# sheet_6.net
KiCad netlist of a schematic drawn in Altium Designer
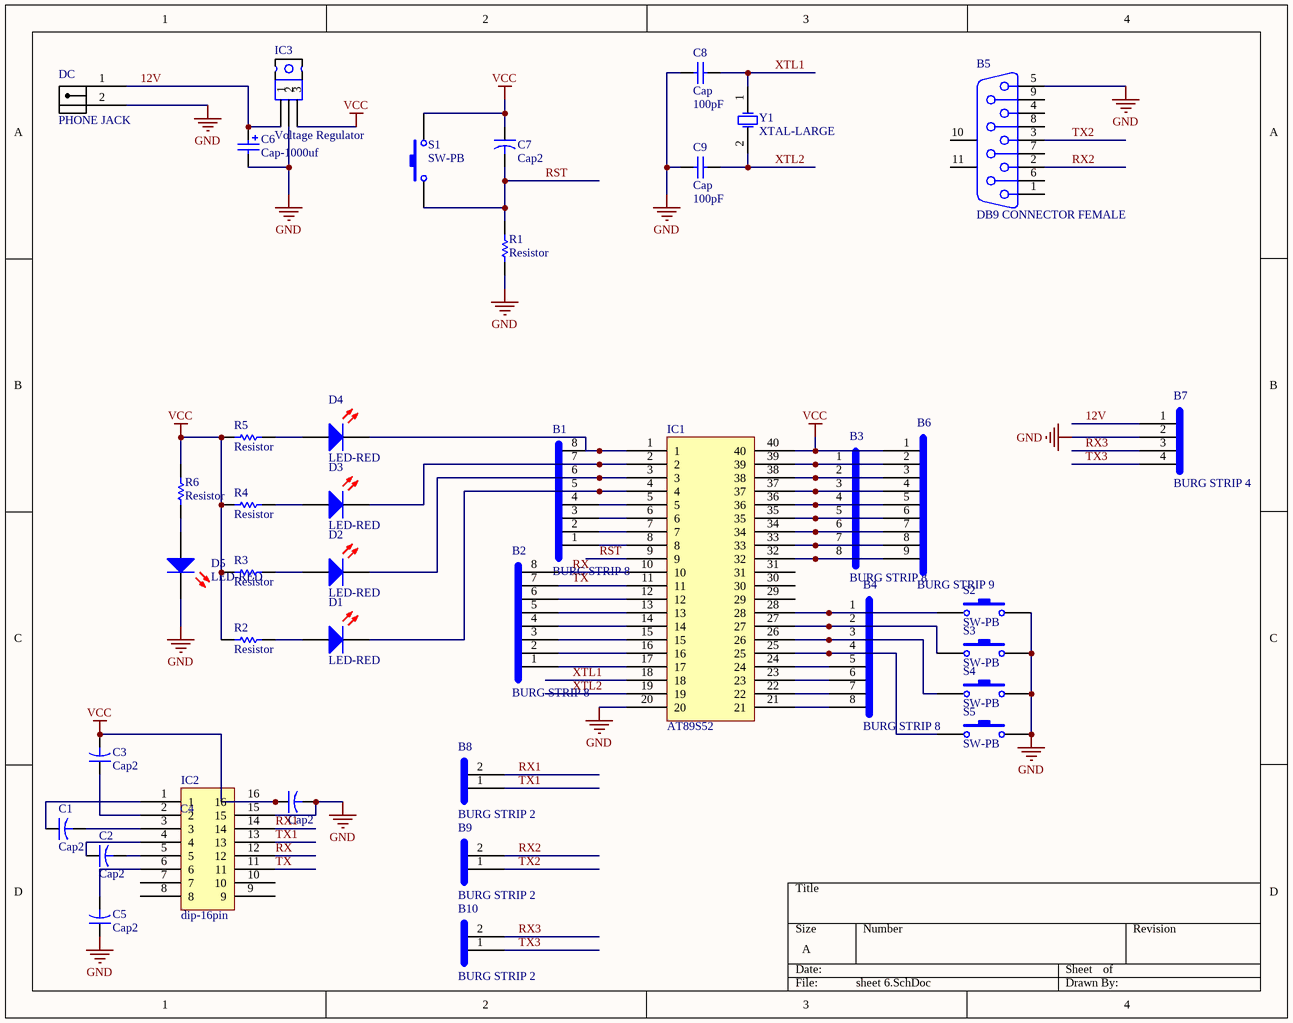
[diagram p0: sheet 6.SchDoc]

(export (version "E")
  (design (tool "Eeschema 10.0.6"))
  (components
    (comp (ref "B1")
      (value "BURG STRIP 8")
      (footprint "bergstrip-8pin")
      (libsource (lib "Devindia_v4.0") (part "BURG STRIP 8"))
    )
    (comp (ref "B2")
      (value "BURG STRIP 8")
      (footprint "bergstrip-8pin")
      (libsource (lib "Devindia_v4.0") (part "BURG STRIP 8"))
    )
    (comp (ref "B3")
      (value "BURG STRIP 8")
      (footprint "bergstrip-8pin")
      (libsource (lib "Devindia_v4.0") (part "BURG STRIP 8"))
    )
    (comp (ref "B4")
      (value "BURG STRIP 8")
      (footprint "bergstrip-8pin")
      (libsource (lib "Devindia_v4.0") (part "BURG STRIP 8"))
    )
    (comp (ref "B5")
      (value "DB9 CONNECTOR FEMALE")
      (footprint "DB9 CONNECTOR FEMALE")
      (libsource (lib "Devindia_v4.0") (part "DB9 CONNECTOR FEMALE"))
    )
    (comp (ref "B6")
      (value "BURG STRIP 9")
      (footprint "bergstrip-9pin")
      (libsource (lib "Devindia_v4.0") (part "BURG STRIP 9"))
    )
    (comp (ref "B7")
      (value "BURG STRIP 4")
      (footprint "bergstrip-4pin")
      (libsource (lib "Devindia_v4.0") (part "BURG STRIP 4"))
    )
    (comp (ref "B8")
      (value "BURG STRIP 2")
      (footprint "bergstrip-2pin")
      (libsource (lib "Devindia_v4.0") (part "BURG STRIP 2"))
    )
    (comp (ref "B9")
      (value "BURG STRIP 2")
      (footprint "bergstrip-2pin")
      (libsource (lib "Devindia_v4.0") (part "BURG STRIP 2"))
    )
    (comp (ref "B10")
      (value "BURG STRIP 2")
      (footprint "bergstrip-2pin")
      (libsource (lib "Devindia_v4.0") (part "BURG STRIP 2"))
    )
    (comp (ref "C1") (value "Cap2") (footprint "CAP-100uf") (libsource (lib "Devindia_v4.0") (part "Cap2")))
    (comp (ref "C2") (value "Cap2") (footprint "CAP-100uf") (libsource (lib "Devindia_v4.0") (part "Cap2")))
    (comp (ref "C3") (value "Cap2") (footprint "CAP-100uf") (libsource (lib "Devindia_v4.0") (part "Cap2")))
    (comp (ref "C4") (value "Cap2") (footprint "CAP-100uf") (libsource (lib "Devindia_v4.0") (part "Cap2")))
    (comp (ref "C5") (value "Cap2") (footprint "CAP-100uf") (libsource (lib "Devindia_v4.0") (part "Cap2")))
    (comp (ref "C6")
      (value "Cap-1000uf")
      (footprint "CAP-1000uf")
      (libsource (lib "Devindia_v4.0") (part "Cap-1000uf"))
    )
    (comp (ref "C7") (value "Cap2") (footprint "CAP-100uf") (libsource (lib "Devindia_v4.0") (part "Cap2")))
    (comp (ref "C8")
      (value "Cap")
      (footprint "CAP")
      (description "Capacitor")
      (fields (field (name "ALTIUM_VALUE") "100pF") (field (name "PUBLISHER") "Altium Limited"))
      (libsource (lib "Devindia_v4.0") (part "Cap"))
    )
    (comp (ref "C9")
      (value "Cap")
      (footprint "CAP")
      (description "Capacitor")
      (fields (field (name "ALTIUM_VALUE") "100pF") (field (name "PUBLISHER") "Altium Limited"))
      (libsource (lib "Devindia_v4.0") (part "Cap"))
    )
    (comp (ref "D1")
      (value "LED-RED")
      (footprint "LED-RED")
      (description "Typical BLUE SiC LED")
      (fields (field (name "PUBLISHER") "Altium Limited"))
      (libsource (lib "Devindia_v4.0") (part "LED-RED"))
    )
    (comp (ref "D2")
      (value "LED-RED")
      (footprint "LED-RED")
      (description "Typical BLUE SiC LED")
      (fields (field (name "PUBLISHER") "Altium Limited"))
      (libsource (lib "Devindia_v4.0") (part "LED-RED"))
    )
    (comp (ref "D3")
      (value "LED-RED")
      (footprint "LED-RED")
      (description "Typical BLUE SiC LED")
      (fields (field (name "PUBLISHER") "Altium Limited"))
      (libsource (lib "Devindia_v4.0") (part "LED-RED"))
    )
    (comp (ref "D4")
      (value "LED-RED")
      (footprint "LED-RED")
      (description "Typical BLUE SiC LED")
      (fields (field (name "PUBLISHER") "Altium Limited"))
      (libsource (lib "Devindia_v4.0") (part "LED-RED"))
    )
    (comp (ref "D5")
      (value "LED-RED")
      (footprint "LED-RED")
      (description "Typical BLUE SiC LED")
      (fields (field (name "PUBLISHER") "Altium Limited"))
      (libsource (lib "Devindia_v4.0") (part "LED-RED"))
    )
    (comp (ref "DC")
      (value "PHONE JACK")
      (footprint "PHONE JACK")
      (libsource (lib "Devindia_v4.0") (part "PHONE JACK"))
    )
    (comp (ref "IC1")
      (value "AT89S52")
      (footprint "AT89S52")
      (libsource (lib "Devindia_v4.0") (part "AT89S52"))
    )
    (comp (ref "IC2")
      (value "dip-16pin")
      (footprint "dip-16pin")
      (libsource (lib "Devindia_v4.0") (part "dip-16pin"))
    )
    (comp (ref "IC3")
      (value "Voltage Regulator")
      (footprint "7805 WITH HEAT-SINK")
      (libsource (lib "Devindia_v4.0") (part "7805 HEATSINK"))
    )
    (comp (ref "R1")
      (value "Resistor")
      (footprint "res-2.54x4")
      (libsource (lib "Devindia_v4.0") (part "Resistor 2.54x4"))
    )
    (comp (ref "R2")
      (value "Resistor")
      (footprint "res-2.54x4")
      (libsource (lib "Devindia_v4.0") (part "Resistor 2.54x4"))
    )
    (comp (ref "R3")
      (value "Resistor")
      (footprint "res-2.54x4")
      (libsource (lib "Devindia_v4.0") (part "Resistor 2.54x4"))
    )
    (comp (ref "R4")
      (value "Resistor")
      (footprint "res-2.54x4")
      (libsource (lib "Devindia_v4.0") (part "Resistor 2.54x4"))
    )
    (comp (ref "R5")
      (value "Resistor")
      (footprint "res-2.54x4")
      (libsource (lib "Devindia_v4.0") (part "Resistor 2.54x4"))
    )
    (comp (ref "R6")
      (value "Resistor")
      (footprint "res-2.54x4")
      (libsource (lib "Devindia_v4.0") (part "Resistor 2.54x4"))
    )
    (comp (ref "S1")
      (value "SW-PB")
      (footprint "sw-pb")
      (description "Switch")
      (fields (field (name "PUBLISHER") "Altium Limited"))
      (libsource (lib "Devindia_v4.0") (part "SW-PB"))
    )
    (comp (ref "S2")
      (value "SW-PB")
      (footprint "sw-pb")
      (description "Switch")
      (fields (field (name "PUBLISHER") "Altium Limited"))
      (libsource (lib "Devindia_v4.0") (part "SW-PB"))
    )
    (comp (ref "S3")
      (value "SW-PB")
      (footprint "sw-pb")
      (description "Switch")
      (fields (field (name "PUBLISHER") "Altium Limited"))
      (libsource (lib "Devindia_v4.0") (part "SW-PB"))
    )
    (comp (ref "S4")
      (value "SW-PB")
      (footprint "sw-pb")
      (description "Switch")
      (fields (field (name "PUBLISHER") "Altium Limited"))
      (libsource (lib "Devindia_v4.0") (part "SW-PB"))
    )
    (comp (ref "S5")
      (value "SW-PB")
      (footprint "sw-pb")
      (description "Switch")
      (fields (field (name "PUBLISHER") "Altium Limited"))
      (libsource (lib "Devindia_v4.0") (part "SW-PB"))
    )
    (comp (ref "Y1")
      (value "XTAL-LARGE")
      (footprint "XTAL-LARGE")
      (description "Crystal Oscillator")
      (fields (field (name "PUBLISHER") "Altium Limited"))
      (libsource (lib "Devindia_v4.0") (part "XTAL-LARGE"))
    )
  )
  (nets
    (net (code "1") (name "/12V") (class "Default")
      (node (ref "B7") (pin "1") (pinfunction "1_1") (pintype "passive"))
      (node (ref "C6") (pin "1") (pinfunction "1_1") (pintype "passive"))
      (node (ref "DC") (pin "1") (pinfunction "1_1") (pintype "passive"))
      (node (ref "IC3") (pin "1") (pinfunction "1_1") (pintype "passive"))
    )
    (net (code "2") (name "/RST") (class "Default")
      (node (ref "C7") (pin "2") (pinfunction "2_2") (pintype "passive"))
      (node (ref "IC1") (pin "9") (pinfunction "9_9") (pintype "passive"))
      (node (ref "R1") (pin "2") (pinfunction "2_2") (pintype "passive"))
      (node (ref "S1") (pin "1") (pinfunction "1_1") (pintype "passive"))
    )
    (net (code "3") (name "/RX") (class "Default")
      (node (ref "B2") (pin "8") (pinfunction "8_8") (pintype "passive"))
      (node (ref "IC1") (pin "10") (pinfunction "10_10") (pintype "passive"))
      (node (ref "IC2") (pin "12") (pinfunction "12_12") (pintype "passive"))
    )
    (net (code "4") (name "/RX1") (class "Default")
      (node (ref "B8") (pin "2") (pinfunction "2_2") (pintype "passive"))
      (node (ref "IC2") (pin "14") (pinfunction "14_14") (pintype "passive"))
    )
    (net (code "5") (name "/RX2") (class "Default")
      (node (ref "B5") (pin "2") (pinfunction "2_2") (pintype "passive"))
      (node (ref "B9") (pin "2") (pinfunction "2_2") (pintype "passive"))
    )
    (net (code "6") (name "/RX3") (class "Default")
      (node (ref "B10") (pin "2") (pinfunction "2_2") (pintype "passive"))
      (node (ref "B7") (pin "3") (pinfunction "3_3") (pintype "passive"))
    )
    (net (code "7") (name "/TX") (class "Default")
      (node (ref "B2") (pin "7") (pinfunction "7_7") (pintype "passive"))
      (node (ref "IC1") (pin "11") (pinfunction "11_11") (pintype "passive"))
      (node (ref "IC2") (pin "11") (pinfunction "11_11") (pintype "passive"))
    )
    (net (code "8") (name "/TX1") (class "Default")
      (node (ref "B8") (pin "1") (pinfunction "1_1") (pintype "passive"))
      (node (ref "IC2") (pin "13") (pinfunction "13_13") (pintype "passive"))
    )
    (net (code "9") (name "/TX2") (class "Default")
      (node (ref "B5") (pin "3") (pinfunction "3_3") (pintype "passive"))
      (node (ref "B9") (pin "1") (pinfunction "1_1") (pintype "passive"))
    )
    (net (code "10") (name "/TX3") (class "Default")
      (node (ref "B10") (pin "1") (pinfunction "1_1") (pintype "passive"))
      (node (ref "B7") (pin "4") (pinfunction "4_4") (pintype "passive"))
    )
    (net (code "11") (name "/XTL1") (class "Default")
      (node (ref "C8") (pin "2") (pinfunction "2_2") (pintype "passive"))
      (node (ref "IC1") (pin "18") (pinfunction "18_18") (pintype "passive"))
      (node (ref "Y1") (pin "1") (pinfunction "OSC1_1") (pintype "passive"))
    )
    (net (code "12") (name "/XTL2") (class "Default")
      (node (ref "C9") (pin "2") (pinfunction "2_2") (pintype "passive"))
      (node (ref "IC1") (pin "19") (pinfunction "19_19") (pintype "passive"))
      (node (ref "Y1") (pin "2") (pinfunction "OSC2_2") (pintype "passive"))
    )
    (net (code "13") (name "GND") (class "Default")
      (node (ref "B5") (pin "5") (pinfunction "5_5") (pintype "passive"))
      (node (ref "B7") (pin "2") (pinfunction "2_2") (pintype "passive"))
      (node (ref "C4") (pin "2") (pinfunction "2_2") (pintype "passive"))
      (node (ref "C5") (pin "1") (pinfunction "1_1") (pintype "passive"))
      (node (ref "C6") (pin "2") (pinfunction "2_2") (pintype "passive"))
      (node (ref "C8") (pin "1") (pinfunction "1_1") (pintype "passive"))
      (node (ref "C9") (pin "1") (pinfunction "1_1") (pintype "passive"))
      (node (ref "D5") (pin "2") (pinfunction "K_2") (pintype "passive"))
      (node (ref "DC") (pin "2") (pinfunction "2_2") (pintype "passive"))
      (node (ref "IC1") (pin "20") (pinfunction "20_20") (pintype "passive"))
      (node (ref "IC2") (pin "15") (pinfunction "15_15") (pintype "passive"))
      (node (ref "IC3") (pin "2") (pinfunction "2_2") (pintype "passive"))
      (node (ref "R1") (pin "1") (pinfunction "1_1") (pintype "passive"))
      (node (ref "S2") (pin "2") (pinfunction "2_2") (pintype "passive"))
      (node (ref "S3") (pin "2") (pinfunction "2_2") (pintype "passive"))
      (node (ref "S4") (pin "2") (pinfunction "2_2") (pintype "passive"))
      (node (ref "S5") (pin "2") (pinfunction "2_2") (pintype "passive"))
    )
    (net (code "14") (name "Net-(B1-Pad1)") (class "Default")
      (node (ref "B1") (pin "1") (pinfunction "1_1") (pintype "passive"))
      (node (ref "IC1") (pin "8") (pinfunction "8_8") (pintype "passive"))
    )
    (net (code "15") (name "Net-(B1-Pad2)") (class "Default")
      (node (ref "B1") (pin "2") (pinfunction "2_2") (pintype "passive"))
      (node (ref "IC1") (pin "7") (pinfunction "7_7") (pintype "passive"))
    )
    (net (code "16") (name "Net-(B1-Pad3)") (class "Default")
      (node (ref "B1") (pin "3") (pinfunction "3_3") (pintype "passive"))
      (node (ref "IC1") (pin "6") (pinfunction "6_6") (pintype "passive"))
    )
    (net (code "17") (name "Net-(B1-Pad4)") (class "Default")
      (node (ref "B1") (pin "4") (pinfunction "4_4") (pintype "passive"))
      (node (ref "IC1") (pin "5") (pinfunction "5_5") (pintype "passive"))
    )
    (net (code "18") (name "Net-(B2-Pad1)") (class "Default")
      (node (ref "B2") (pin "1") (pinfunction "1_1") (pintype "passive"))
      (node (ref "IC1") (pin "17") (pinfunction "17_17") (pintype "passive"))
    )
    (net (code "19") (name "Net-(B2-Pad2)") (class "Default")
      (node (ref "B2") (pin "2") (pinfunction "2_2") (pintype "passive"))
      (node (ref "IC1") (pin "16") (pinfunction "16_16") (pintype "passive"))
    )
    (net (code "20") (name "Net-(B2-Pad3)") (class "Default")
      (node (ref "B2") (pin "3") (pinfunction "3_3") (pintype "passive"))
      (node (ref "IC1") (pin "15") (pinfunction "15_15") (pintype "passive"))
    )
    (net (code "21") (name "Net-(B2-Pad4)") (class "Default")
      (node (ref "B2") (pin "4") (pinfunction "4_4") (pintype "passive"))
      (node (ref "IC1") (pin "14") (pinfunction "14_14") (pintype "passive"))
    )
    (net (code "22") (name "Net-(B2-Pad5)") (class "Default")
      (node (ref "B2") (pin "5") (pinfunction "5_5") (pintype "passive"))
      (node (ref "IC1") (pin "13") (pinfunction "13_13") (pintype "passive"))
    )
    (net (code "23") (name "Net-(B2-Pad6)") (class "Default")
      (node (ref "B2") (pin "6") (pinfunction "6_6") (pintype "passive"))
      (node (ref "IC1") (pin "12") (pinfunction "12_12") (pintype "passive"))
    )
    (net (code "24") (name "Net-(B3-Pad1)") (class "Default")
      (node (ref "B3") (pin "1") (pinfunction "1_1") (pintype "passive"))
      (node (ref "B6") (pin "2") (pinfunction "2_2") (pintype "passive"))
      (node (ref "IC1") (pin "39") (pinfunction "39_39") (pintype "passive"))
    )
    (net (code "25") (name "Net-(B3-Pad2)") (class "Default")
      (node (ref "B3") (pin "2") (pinfunction "2_2") (pintype "passive"))
      (node (ref "B6") (pin "3") (pinfunction "3_3") (pintype "passive"))
      (node (ref "IC1") (pin "38") (pinfunction "38_38") (pintype "passive"))
    )
    (net (code "26") (name "Net-(B3-Pad3)") (class "Default")
      (node (ref "B3") (pin "3") (pinfunction "3_3") (pintype "passive"))
      (node (ref "B6") (pin "4") (pinfunction "4_4") (pintype "passive"))
      (node (ref "IC1") (pin "37") (pinfunction "37_37") (pintype "passive"))
    )
    (net (code "27") (name "Net-(B3-Pad4)") (class "Default")
      (node (ref "B3") (pin "4") (pinfunction "4_4") (pintype "passive"))
      (node (ref "B6") (pin "5") (pinfunction "5_5") (pintype "passive"))
      (node (ref "IC1") (pin "36") (pinfunction "36_36") (pintype "passive"))
    )
    (net (code "28") (name "Net-(B3-Pad5)") (class "Default")
      (node (ref "B3") (pin "5") (pinfunction "5_5") (pintype "passive"))
      (node (ref "B6") (pin "6") (pinfunction "6_6") (pintype "passive"))
      (node (ref "IC1") (pin "35") (pinfunction "35_35") (pintype "passive"))
    )
    (net (code "29") (name "Net-(B3-Pad6)") (class "Default")
      (node (ref "B3") (pin "6") (pinfunction "6_6") (pintype "passive"))
      (node (ref "B6") (pin "7") (pinfunction "7_7") (pintype "passive"))
      (node (ref "IC1") (pin "34") (pinfunction "34_34") (pintype "passive"))
    )
    (net (code "30") (name "Net-(B3-Pad7)") (class "Default")
      (node (ref "B3") (pin "7") (pinfunction "7_7") (pintype "passive"))
      (node (ref "B6") (pin "8") (pinfunction "8_8") (pintype "passive"))
      (node (ref "IC1") (pin "33") (pinfunction "33_33") (pintype "passive"))
    )
    (net (code "31") (name "Net-(B3-Pad8)") (class "Default")
      (node (ref "B3") (pin "8") (pinfunction "8_8") (pintype "passive"))
      (node (ref "B6") (pin "9") (pinfunction "9_9") (pintype "passive"))
      (node (ref "IC1") (pin "32") (pinfunction "32_32") (pintype "passive"))
    )
    (net (code "32") (name "Net-(B4-Pad1)") (class "Default")
      (node (ref "B4") (pin "1") (pinfunction "1_1") (pintype "passive"))
      (node (ref "IC1") (pin "28") (pinfunction "28_28") (pintype "passive"))
      (node (ref "S2") (pin "1") (pinfunction "1_1") (pintype "passive"))
    )
    (net (code "33") (name "Net-(B4-Pad2)") (class "Default")
      (node (ref "B4") (pin "2") (pinfunction "2_2") (pintype "passive"))
      (node (ref "IC1") (pin "27") (pinfunction "27_27") (pintype "passive"))
      (node (ref "S3") (pin "1") (pinfunction "1_1") (pintype "passive"))
    )
    (net (code "34") (name "Net-(B4-Pad3)") (class "Default")
      (node (ref "B4") (pin "3") (pinfunction "3_3") (pintype "passive"))
      (node (ref "IC1") (pin "26") (pinfunction "26_26") (pintype "passive"))
      (node (ref "S4") (pin "1") (pinfunction "1_1") (pintype "passive"))
    )
    (net (code "35") (name "Net-(B4-Pad4)") (class "Default")
      (node (ref "B4") (pin "4") (pinfunction "4_4") (pintype "passive"))
      (node (ref "IC1") (pin "25") (pinfunction "25_25") (pintype "passive"))
      (node (ref "S5") (pin "1") (pinfunction "1_1") (pintype "passive"))
    )
    (net (code "36") (name "Net-(B4-Pad5)") (class "Default")
      (node (ref "B4") (pin "5") (pinfunction "5_5") (pintype "passive"))
      (node (ref "IC1") (pin "24") (pinfunction "24_24") (pintype "passive"))
    )
    (net (code "37") (name "Net-(B4-Pad6)") (class "Default")
      (node (ref "B4") (pin "6") (pinfunction "6_6") (pintype "passive"))
      (node (ref "IC1") (pin "23") (pinfunction "23_23") (pintype "passive"))
    )
    (net (code "38") (name "Net-(B4-Pad7)") (class "Default")
      (node (ref "B4") (pin "7") (pinfunction "7_7") (pintype "passive"))
      (node (ref "IC1") (pin "22") (pinfunction "22_22") (pintype "passive"))
    )
    (net (code "39") (name "Net-(B4-Pad8)") (class "Default")
      (node (ref "B4") (pin "8") (pinfunction "8_8") (pintype "passive"))
      (node (ref "IC1") (pin "21") (pinfunction "21_21") (pintype "passive"))
    )
    (net (code "40") (name "Net-(C1-Pad1)") (class "Default")
      (node (ref "C1") (pin "1") (pinfunction "1_1") (pintype "passive"))
      (node (ref "IC2") (pin "1") (pinfunction "1_1") (pintype "passive"))
    )
    (net (code "41") (name "Net-(C1-Pad2)") (class "Default")
      (node (ref "C1") (pin "2") (pinfunction "2_2") (pintype "passive"))
      (node (ref "IC2") (pin "3") (pinfunction "3_3") (pintype "passive"))
    )
    (net (code "42") (name "Net-(C2-Pad1)") (class "Default")
      (node (ref "C2") (pin "1") (pinfunction "1_1") (pintype "passive"))
      (node (ref "IC2") (pin "4") (pinfunction "4_4") (pintype "passive"))
    )
    (net (code "43") (name "Net-(C2-Pad2)") (class "Default")
      (node (ref "C2") (pin "2") (pinfunction "2_2") (pintype "passive"))
      (node (ref "IC2") (pin "5") (pinfunction "5_5") (pintype "passive"))
    )
    (net (code "44") (name "Net-(C3-Pad1)") (class "Default")
      (node (ref "C3") (pin "1") (pinfunction "1_1") (pintype "passive"))
      (node (ref "IC2") (pin "2") (pinfunction "2_2") (pintype "passive"))
    )
    (net (code "45") (name "Net-(C5-Pad2)") (class "Default")
      (node (ref "C5") (pin "2") (pinfunction "2_2") (pintype "passive"))
      (node (ref "IC2") (pin "6") (pinfunction "6_6") (pintype "passive"))
    )
    (net (code "46") (name "Net-(D1-A)") (class "Default")
      (node (ref "D1") (pin "1") (pinfunction "A_1") (pintype "passive"))
      (node (ref "R2") (pin "2") (pinfunction "2_2") (pintype "passive"))
    )
    (net (code "47") (name "Net-(D1-K)") (class "Default")
      (node (ref "B1") (pin "5") (pinfunction "5_5") (pintype "passive"))
      (node (ref "D1") (pin "2") (pinfunction "K_2") (pintype "passive"))
      (node (ref "IC1") (pin "4") (pinfunction "4_4") (pintype "passive"))
    )
    (net (code "48") (name "Net-(D2-A)") (class "Default")
      (node (ref "D2") (pin "1") (pinfunction "A_1") (pintype "passive"))
      (node (ref "R3") (pin "2") (pinfunction "2_2") (pintype "passive"))
    )
    (net (code "49") (name "Net-(D2-K)") (class "Default")
      (node (ref "B1") (pin "6") (pinfunction "6_6") (pintype "passive"))
      (node (ref "D2") (pin "2") (pinfunction "K_2") (pintype "passive"))
      (node (ref "IC1") (pin "3") (pinfunction "3_3") (pintype "passive"))
    )
    (net (code "50") (name "Net-(D3-A)") (class "Default")
      (node (ref "D3") (pin "1") (pinfunction "A_1") (pintype "passive"))
      (node (ref "R4") (pin "2") (pinfunction "2_2") (pintype "passive"))
    )
    (net (code "51") (name "Net-(D3-K)") (class "Default")
      (node (ref "B1") (pin "7") (pinfunction "7_7") (pintype "passive"))
      (node (ref "D3") (pin "2") (pinfunction "K_2") (pintype "passive"))
      (node (ref "IC1") (pin "2") (pinfunction "2_2") (pintype "passive"))
    )
    (net (code "52") (name "Net-(D4-A)") (class "Default")
      (node (ref "D4") (pin "1") (pinfunction "A_1") (pintype "passive"))
      (node (ref "R5") (pin "2") (pinfunction "2_2") (pintype "passive"))
    )
    (net (code "53") (name "Net-(D4-K)") (class "Default")
      (node (ref "B1") (pin "8") (pinfunction "8_8") (pintype "passive"))
      (node (ref "D4") (pin "2") (pinfunction "K_2") (pintype "passive"))
      (node (ref "IC1") (pin "1") (pinfunction "1_1") (pintype "passive"))
    )
    (net (code "54") (name "Net-(D5-A)") (class "Default")
      (node (ref "D5") (pin "1") (pinfunction "A_1") (pintype "passive"))
      (node (ref "R6") (pin "1") (pinfunction "1_1") (pintype "passive"))
    )
    (net (code "55") (name "VCC") (class "Default")
      (node (ref "B6") (pin "1") (pinfunction "1_1") (pintype "passive"))
      (node (ref "C3") (pin "2") (pinfunction "2_2") (pintype "passive"))
      (node (ref "C4") (pin "1") (pinfunction "1_1") (pintype "passive"))
      (node (ref "C7") (pin "1") (pinfunction "1_1") (pintype "passive"))
      (node (ref "IC1") (pin "40") (pinfunction "40_40") (pintype "passive"))
      (node (ref "IC2") (pin "16") (pinfunction "16_16") (pintype "passive"))
      (node (ref "IC3") (pin "3") (pinfunction "3_3") (pintype "passive"))
      (node (ref "R2") (pin "1") (pinfunction "1_1") (pintype "passive"))
      (node (ref "R3") (pin "1") (pinfunction "1_1") (pintype "passive"))
      (node (ref "R4") (pin "1") (pinfunction "1_1") (pintype "passive"))
      (node (ref "R5") (pin "1") (pinfunction "1_1") (pintype "passive"))
      (node (ref "R6") (pin "2") (pinfunction "2_2") (pintype "passive"))
      (node (ref "S1") (pin "2") (pinfunction "2_2") (pintype "passive"))
    )
    (net (code "56") (name "unconnected-(B5-MH1-Pad10)") (class "Default")
      (node (ref "B5") (pin "10") (pinfunction "MH1_10") (pintype "passive"))
    )
    (net (code "57") (name "unconnected-(B5-MH2-Pad11)") (class "Default")
      (node (ref "B5") (pin "11") (pinfunction "MH2_11") (pintype "passive"))
    )
    (net (code "58") (name "unconnected-(B5-Pad1)") (class "Default")
      (node (ref "B5") (pin "1") (pinfunction "1_1") (pintype "passive"))
    )
    (net (code "59") (name "unconnected-(B5-Pad4)") (class "Default")
      (node (ref "B5") (pin "4") (pinfunction "4_4") (pintype "passive"))
    )
    (net (code "60") (name "unconnected-(B5-Pad6)") (class "Default")
      (node (ref "B5") (pin "6") (pinfunction "6_6") (pintype "passive"))
    )
    (net (code "61") (name "unconnected-(B5-Pad7)") (class "Default")
      (node (ref "B5") (pin "7") (pinfunction "7_7") (pintype "passive"))
    )
    (net (code "62") (name "unconnected-(B5-Pad8)") (class "Default")
      (node (ref "B5") (pin "8") (pinfunction "8_8") (pintype "passive"))
    )
    (net (code "63") (name "unconnected-(B5-Pad9)") (class "Default")
      (node (ref "B5") (pin "9") (pinfunction "9_9") (pintype "passive"))
    )
    (net (code "64") (name "unconnected-(IC1-Pad29)") (class "Default")
      (node (ref "IC1") (pin "29") (pinfunction "29_29") (pintype "passive"))
    )
    (net (code "65") (name "unconnected-(IC1-Pad30)") (class "Default")
      (node (ref "IC1") (pin "30") (pinfunction "30_30") (pintype "passive"))
    )
    (net (code "66") (name "unconnected-(IC1-Pad31)") (class "Default")
      (node (ref "IC1") (pin "31") (pinfunction "31_31") (pintype "passive"))
    )
    (net (code "67") (name "unconnected-(IC2-Pad7)") (class "Default")
      (node (ref "IC2") (pin "7") (pinfunction "7_7") (pintype "passive"))
    )
    (net (code "68") (name "unconnected-(IC2-Pad8)") (class "Default")
      (node (ref "IC2") (pin "8") (pinfunction "8_8") (pintype "passive"))
    )
    (net (code "69") (name "unconnected-(IC2-Pad9)") (class "Default")
      (node (ref "IC2") (pin "9") (pinfunction "9_9") (pintype "passive"))
    )
    (net (code "70") (name "unconnected-(IC2-Pad10)") (class "Default")
      (node (ref "IC2") (pin "10") (pinfunction "10_10") (pintype "passive"))
    )
  )
)
